# SparkFun_Qwiic_ToF_Imager_-_VL53L5CX.net
KiCad netlist of a schematic drawn in EAGLE
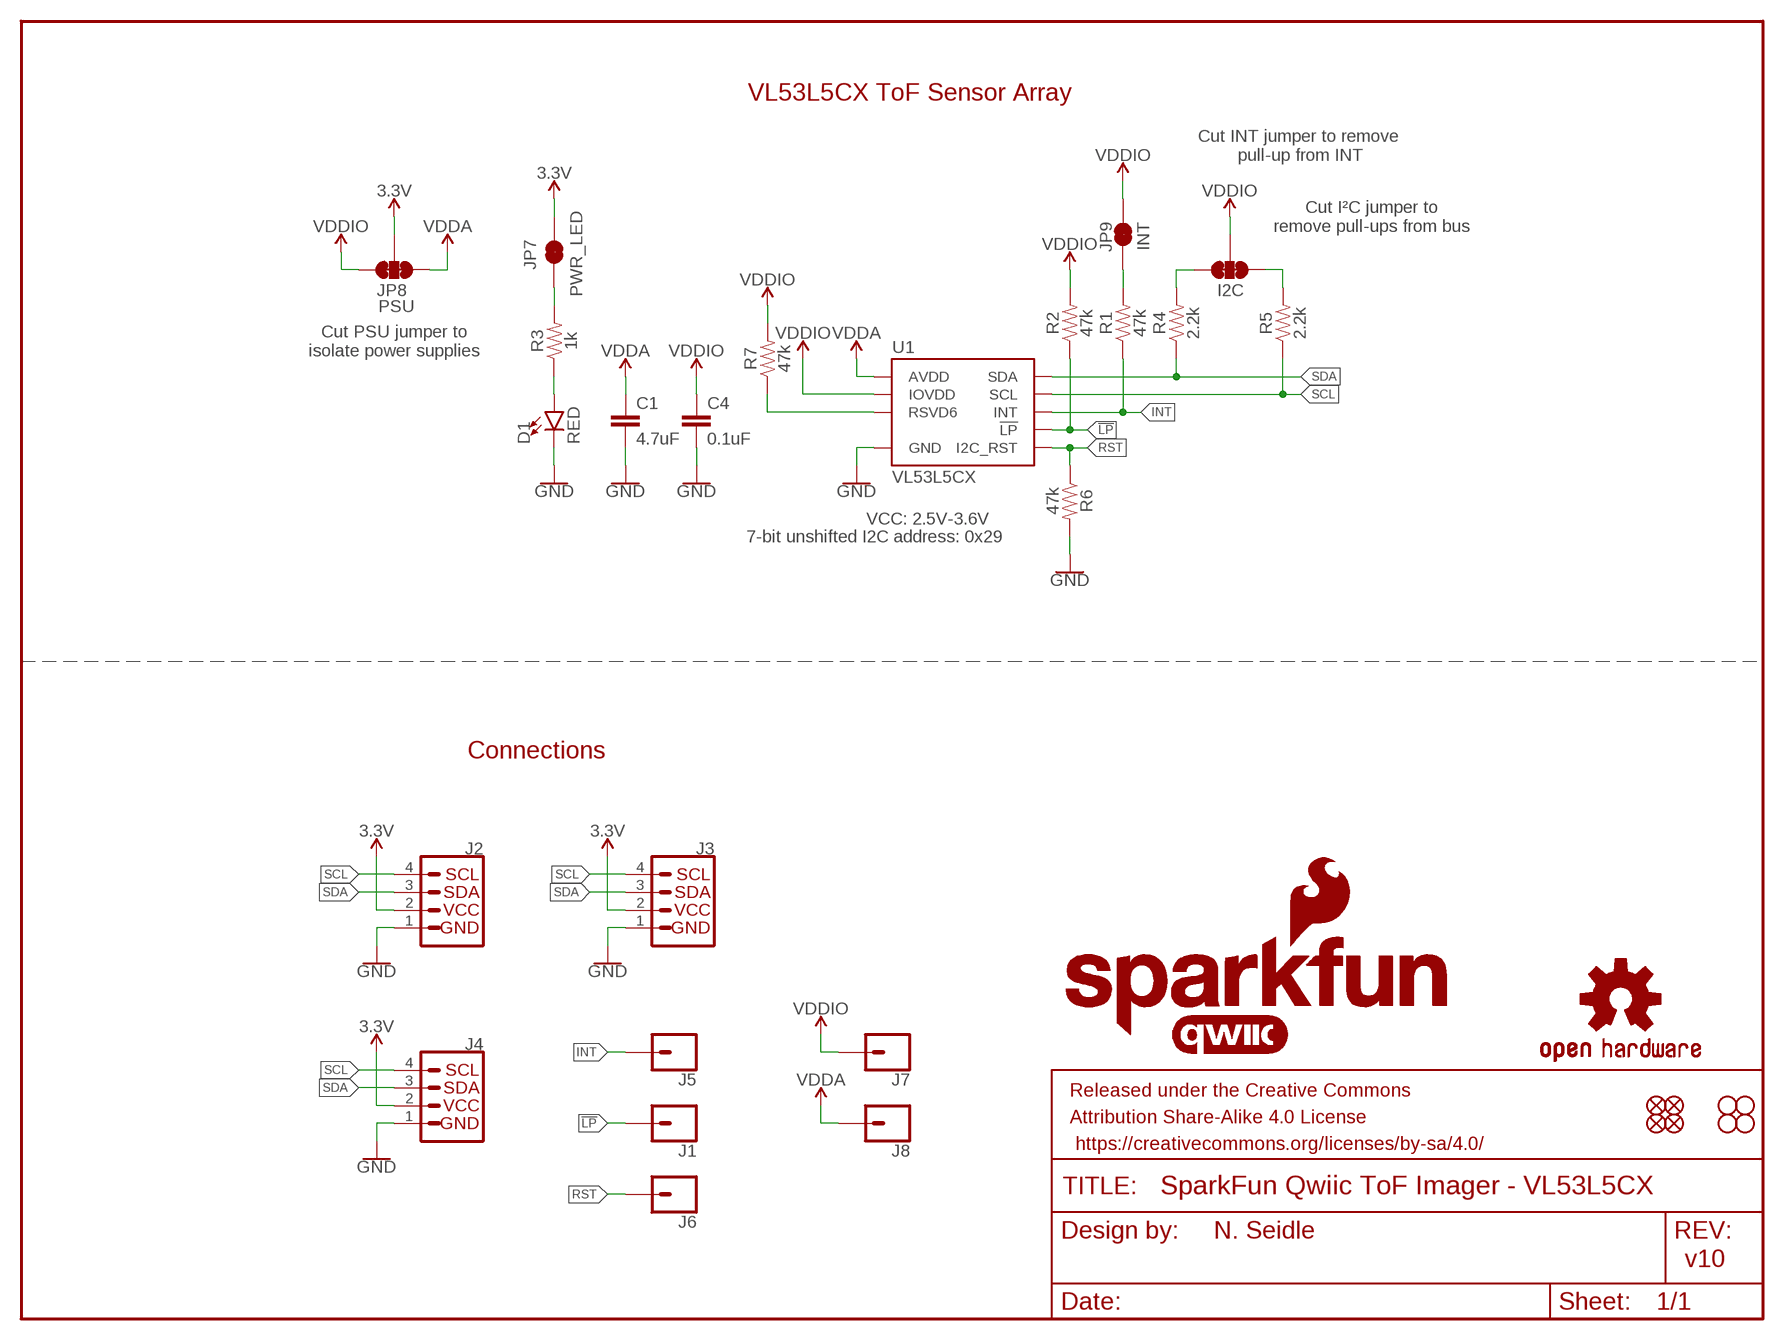
[diagram p0: schematic, sheet 1]

(export (version "E")
  (design (tool "Eeschema 10.0.6"))
  (components
    (comp (ref "C1")
      (value "4.7uF")
      (footprint "eagle-import:0603")
      (libsource (lib "eagle-import") (part "4.7UF-0603-6.3V-(10%)"))
    )
    (comp (ref "C4")
      (value "0.1uF")
      (footprint "eagle-import:0603")
      (libsource (lib "eagle-import") (part "0.1UF-0603-25V-(+80/-20%)"))
    )
    (comp (ref "D1")
      (value "RED")
      (footprint "eagle-import:LED-0603")
      (libsource (lib "eagle-import") (part "LED-RED0603"))
    )
    (comp (ref "FRAME1")
      (value "FRAME-LETTER")
      (footprint "eagle-import:CREATIVE_COMMONS")
      (libsource (lib "eagle-import") (part "FRAME-LETTER"))
    )
    (comp (ref "I2C")
      (value "JUMPER-SMT_3_2-NC_TRACE_SILK")
      (footprint "eagle-import:SMT-JUMPER_3_2-NC_TRACE_SILK")
      (libsource (lib "eagle-import") (part "JUMPER-SMT_3_2-NC_TRACE_SILK"))
    )
    (comp (ref "J1")
      (value "CONN_01PTH_NO_SILK_YES_STOP")
      (footprint "eagle-import:1X01_NO_SILK")
      (libsource (lib "eagle-import") (part "CONN_01PTH_NO_SILK_YES_STOP"))
    )
    (comp (ref "J2")
      (value "QWIIC_CONNECTORJS-1MM")
      (footprint "eagle-import:JST04_1MM_RA")
      (libsource (lib "eagle-import") (part "QWIIC_CONNECTORJS-1MM"))
    )
    (comp (ref "J3")
      (value "PTH")
      (footprint "eagle-import:1X04_NO_SILK")
      (libsource (lib "eagle-import") (part "I2C_STANDARD_NO_SILK"))
    )
    (comp (ref "J4")
      (value "QWIIC_CONNECTORJS-1MM")
      (footprint "eagle-import:JST04_1MM_RA")
      (libsource (lib "eagle-import") (part "QWIIC_CONNECTORJS-1MM"))
    )
    (comp (ref "J5")
      (value "CONN_01PTH_NO_SILK_YES_STOP")
      (footprint "eagle-import:1X01_NO_SILK")
      (libsource (lib "eagle-import") (part "CONN_01PTH_NO_SILK_YES_STOP"))
    )
    (comp (ref "J6")
      (value "CONN_01PTH_NO_SILK_YES_STOP")
      (footprint "eagle-import:1X01_NO_SILK")
      (libsource (lib "eagle-import") (part "CONN_01PTH_NO_SILK_YES_STOP"))
    )
    (comp (ref "J7")
      (value "CONN_01PTH_NO_SILK_YES_STOP")
      (footprint "eagle-import:1X01_NO_SILK")
      (libsource (lib "eagle-import") (part "CONN_01PTH_NO_SILK_YES_STOP"))
    )
    (comp (ref "J8")
      (value "CONN_01PTH_NO_SILK_YES_STOP")
      (footprint "eagle-import:1X01_NO_SILK")
      (libsource (lib "eagle-import") (part "CONN_01PTH_NO_SILK_YES_STOP"))
    )
    (comp (ref "JP1")
      (value "FIDUCIALUFIDUCIAL")
      (footprint "eagle-import:MICRO-FIDUCIAL")
      (libsource (lib "eagle-import") (part "FIDUCIALUFIDUCIAL"))
    )
    (comp (ref "JP2")
      (value "FIDUCIALUFIDUCIAL")
      (footprint "eagle-import:MICRO-FIDUCIAL")
      (libsource (lib "eagle-import") (part "FIDUCIALUFIDUCIAL"))
    )
    (comp (ref "JP3")
      (value "STAND-OFF")
      (footprint "eagle-import:STAND-OFF")
      (libsource (lib "eagle-import") (part "STAND-OFF"))
    )
    (comp (ref "JP4")
      (value "STAND-OFF")
      (footprint "eagle-import:STAND-OFF")
      (libsource (lib "eagle-import") (part "STAND-OFF"))
    )
    (comp (ref "JP5")
      (value "FIDUCIALUFIDUCIAL")
      (footprint "eagle-import:MICRO-FIDUCIAL")
      (libsource (lib "eagle-import") (part "FIDUCIALUFIDUCIAL"))
    )
    (comp (ref "JP6")
      (value "FIDUCIALUFIDUCIAL")
      (footprint "eagle-import:MICRO-FIDUCIAL")
      (libsource (lib "eagle-import") (part "FIDUCIALUFIDUCIAL"))
    )
    (comp (ref "JP7")
      (value "PWR_LED")
      (footprint "eagle-import:SMT-JUMPER_2_NC_TRACE_SILK")
      (libsource (lib "eagle-import") (part "JUMPER-SMT_2_NC_TRACE_SILK"))
    )
    (comp (ref "JP8")
      (value "PSU")
      (footprint "eagle-import:SMT-JUMPER_3_2-NC_TRACE_SILK")
      (libsource (lib "eagle-import") (part "JUMPER-SMT_3_2-NC_TRACE_SILK"))
    )
    (comp (ref "JP9")
      (value "INT")
      (footprint "eagle-import:SMT-JUMPER_2_NC_TRACE_SILK")
      (libsource (lib "eagle-import") (part "JUMPER-SMT_2_NC_TRACE_SILK"))
    )
    (comp (ref "JP10")
      (value "STAND-OFF")
      (footprint "eagle-import:STAND-OFF")
      (libsource (lib "eagle-import") (part "STAND-OFF"))
    )
    (comp (ref "JP11")
      (value "STAND-OFF")
      (footprint "eagle-import:STAND-OFF")
      (libsource (lib "eagle-import") (part "STAND-OFF"))
    )
    (comp (ref "LOGO1")
      (value "OSHW-LOGOMINI")
      (footprint "eagle-import:OSHW-LOGO-MINI")
      (libsource (lib "eagle-import") (part "OSHW-LOGOMINI"))
    )
    (comp (ref "LOGO3")
      (value "QWIIC_LOGO_CONNECTOR")
      (footprint "eagle-import:QWIIC_5.5MM")
      (libsource (lib "eagle-import") (part "QWIIC_LOGO_CONNECTOR"))
    )
    (comp (ref "R1")
      (value "47k")
      (footprint "eagle-import:0603")
      (libsource (lib "eagle-import") (part "47KOHM-0603-1/10W-1%"))
    )
    (comp (ref "R2")
      (value "47k")
      (footprint "eagle-import:0603")
      (libsource (lib "eagle-import") (part "47KOHM-0603-1/10W-1%"))
    )
    (comp (ref "R3")
      (value "1k")
      (footprint "eagle-import:0603")
      (libsource (lib "eagle-import") (part "1KOHM-0603-1/10W-1%"))
    )
    (comp (ref "R4")
      (value "2.2k")
      (footprint "eagle-import:0603")
      (libsource (lib "eagle-import") (part "2.2KOHM-0603-1/10W-1%"))
    )
    (comp (ref "R5")
      (value "2.2k")
      (footprint "eagle-import:0603")
      (libsource (lib "eagle-import") (part "2.2KOHM-0603-1/10W-1%"))
    )
    (comp (ref "R6")
      (value "47k")
      (footprint "eagle-import:0603")
      (libsource (lib "eagle-import") (part "47KOHM-0603-1/10W-1%"))
    )
    (comp (ref "R7")
      (value "47k")
      (footprint "eagle-import:0603")
      (libsource (lib "eagle-import") (part "47KOHM-0603-1/10W-1%"))
    )
    (comp (ref "U$1")
      (value "SFE_LOGO_NAME.1_INCH")
      (footprint "eagle-import:SFE_LOGO_NAME_.1")
      (libsource (lib "eagle-import") (part "SFE_LOGO_NAME.1_INCH"))
    )
    (comp (ref "U$2")
      (value "SFE_LOGO_NAME_FLAME.1_INCH")
      (footprint "eagle-import:SFE_LOGO_NAME_FLAME_.1")
      (libsource (lib "eagle-import") (part "SFE_LOGO_NAME_FLAME.1_INCH"))
    )
    (comp (ref "U1")
      (value "VL53L5CX")
      (footprint "eagle-import:VL53L5CX")
      (libsource (lib "eagle-import") (part "VL53L5CX"))
    )
  )
  (nets
    (net (code "1") (name "/~{LP}") (class "Default")
      (node (ref "J1") (pin "1") (pinfunction "1_1") (pintype "passive"))
      (node (ref "R2") (pin "1") (pinfunction "1_1") (pintype "passive"))
      (node (ref "U1") (pin "A5") (pinfunction "~{LP}_A5") (pintype "bidirectional"))
    )
    (net (code "2") (name "3.3V") (class "Default")
      (node (ref "J2") (pin "2") (pinfunction "2_2") (pintype "power_in"))
      (node (ref "J3") (pin "2") (pinfunction "VCC_2") (pintype "power_in"))
      (node (ref "J4") (pin "2") (pinfunction "2_2") (pintype "power_in"))
      (node (ref "JP7") (pin "2") (pinfunction "2_2") (pintype "passive"))
      (node (ref "JP8") (pin "2") (pinfunction "2_2") (pintype "passive"))
    )
    (net (code "3") (name "GND") (class "Default")
      (node (ref "C1") (pin "2") (pinfunction "2_2") (pintype "passive"))
      (node (ref "C4") (pin "2") (pinfunction "2_2") (pintype "passive"))
      (node (ref "D1") (pin "C") (pinfunction "C_C") (pintype "passive"))
      (node (ref "J2") (pin "1") (pinfunction "1_1") (pintype "power_in"))
      (node (ref "J3") (pin "1") (pinfunction "GND_1") (pintype "power_in"))
      (node (ref "J4") (pin "1") (pinfunction "1_1") (pintype "power_in"))
      (node (ref "R6") (pin "2") (pinfunction "2_2") (pintype "passive"))
      (node (ref "U1") (pin "A2") (pinfunction "GND_A2") (pintype "bidirectional"))
      (node (ref "U1") (pin "A6") (pinfunction "GND_A6") (pintype "bidirectional"))
      (node (ref "U1") (pin "A7") (pinfunction "GND_A7") (pintype "bidirectional"))
      (node (ref "U1") (pin "B4") (pinfunction "GND_B4") (pintype "bidirectional"))
      (node (ref "U1") (pin "C1") (pinfunction "GND_C1") (pintype "bidirectional"))
      (node (ref "U1") (pin "C6") (pinfunction "GND_C6") (pintype "bidirectional"))
      (node (ref "U1") (pin "C7") (pinfunction "GND_C7") (pintype "bidirectional"))
    )
    (net (code "4") (name "INT") (class "Default")
      (node (ref "J5") (pin "1") (pinfunction "1_1") (pintype "passive"))
      (node (ref "R1") (pin "1") (pinfunction "1_1") (pintype "passive"))
      (node (ref "U1") (pin "A3") (pinfunction "INT_A3") (pintype "bidirectional"))
    )
    (net (code "5") (name "Net-(D1-PadA)") (class "Default")
      (node (ref "D1") (pin "A") (pinfunction "A_A") (pintype "passive"))
      (node (ref "R3") (pin "1") (pinfunction "1_1") (pintype "passive"))
    )
    (net (code "6") (name "Net-(I2C-Pad1)") (class "Default")
      (node (ref "I2C") (pin "1") (pinfunction "1_1") (pintype "passive"))
      (node (ref "R5") (pin "2") (pinfunction "2_2") (pintype "passive"))
    )
    (net (code "7") (name "Net-(I2C-Pad3)") (class "Default")
      (node (ref "I2C") (pin "3") (pinfunction "3_3") (pintype "passive"))
      (node (ref "R4") (pin "2") (pinfunction "2_2") (pintype "passive"))
    )
    (net (code "8") (name "Net-(JP7-Pad1)") (class "Default")
      (node (ref "JP7") (pin "1") (pinfunction "1_1") (pintype "passive"))
      (node (ref "R3") (pin "2") (pinfunction "2_2") (pintype "passive"))
    )
    (net (code "9") (name "Net-(JP9-Pad1)") (class "Default")
      (node (ref "JP9") (pin "1") (pinfunction "1_1") (pintype "passive"))
      (node (ref "R1") (pin "2") (pinfunction "2_2") (pintype "passive"))
    )
    (net (code "10") (name "Net-(U1-RSVD6)") (class "Default")
      (node (ref "R7") (pin "1") (pinfunction "1_1") (pintype "passive"))
      (node (ref "U1") (pin "C2") (pinfunction "RSVD6_C2") (pintype "bidirectional"))
    )
    (net (code "11") (name "RST") (class "Default")
      (node (ref "J6") (pin "1") (pinfunction "1_1") (pintype "passive"))
      (node (ref "R6") (pin "1") (pinfunction "1_1") (pintype "passive"))
      (node (ref "U1") (pin "A1") (pinfunction "I2C_RST_A1") (pintype "bidirectional"))
    )
    (net (code "12") (name "SCL") (class "Default")
      (node (ref "J2") (pin "4") (pinfunction "4_4") (pintype "passive"))
      (node (ref "J3") (pin "4") (pinfunction "SCL_4") (pintype "passive"))
      (node (ref "J4") (pin "4") (pinfunction "4_4") (pintype "passive"))
      (node (ref "R5") (pin "1") (pinfunction "1_1") (pintype "passive"))
      (node (ref "U1") (pin "C4") (pinfunction "SCL_C4") (pintype "bidirectional"))
    )
    (net (code "13") (name "SDA") (class "Default")
      (node (ref "J2") (pin "3") (pinfunction "3_3") (pintype "passive"))
      (node (ref "J3") (pin "3") (pinfunction "SDA_3") (pintype "passive"))
      (node (ref "J4") (pin "3") (pinfunction "3_3") (pintype "passive"))
      (node (ref "R4") (pin "1") (pinfunction "1_1") (pintype "passive"))
      (node (ref "U1") (pin "C3") (pinfunction "SDA_C3") (pintype "bidirectional"))
    )
    (net (code "14") (name "VDDA") (class "Default")
      (node (ref "C1") (pin "1") (pinfunction "1_1") (pintype "passive"))
      (node (ref "J8") (pin "1") (pinfunction "1_1") (pintype "passive"))
      (node (ref "JP8") (pin "1") (pinfunction "1_1") (pintype "passive"))
      (node (ref "U1") (pin "B1") (pinfunction "AVDD_B1") (pintype "bidirectional"))
      (node (ref "U1") (pin "B7") (pinfunction "AVDD_B7") (pintype "bidirectional"))
    )
    (net (code "15") (name "VDDIO") (class "Default")
      (node (ref "C4") (pin "1") (pinfunction "1_1") (pintype "passive"))
      (node (ref "I2C") (pin "2") (pinfunction "2_2") (pintype "passive"))
      (node (ref "J7") (pin "1") (pinfunction "1_1") (pintype "passive"))
      (node (ref "JP8") (pin "3") (pinfunction "3_3") (pintype "passive"))
      (node (ref "JP9") (pin "2") (pinfunction "2_2") (pintype "passive"))
      (node (ref "R2") (pin "2") (pinfunction "2_2") (pintype "passive"))
      (node (ref "R7") (pin "2") (pinfunction "2_2") (pintype "passive"))
      (node (ref "U1") (pin "A4") (pinfunction "IOVDD_A4") (pintype "bidirectional"))
    )
  )
)
